# modFOC-Sensing.net
KiCad netlist of a schematic drawn in Altium Designer
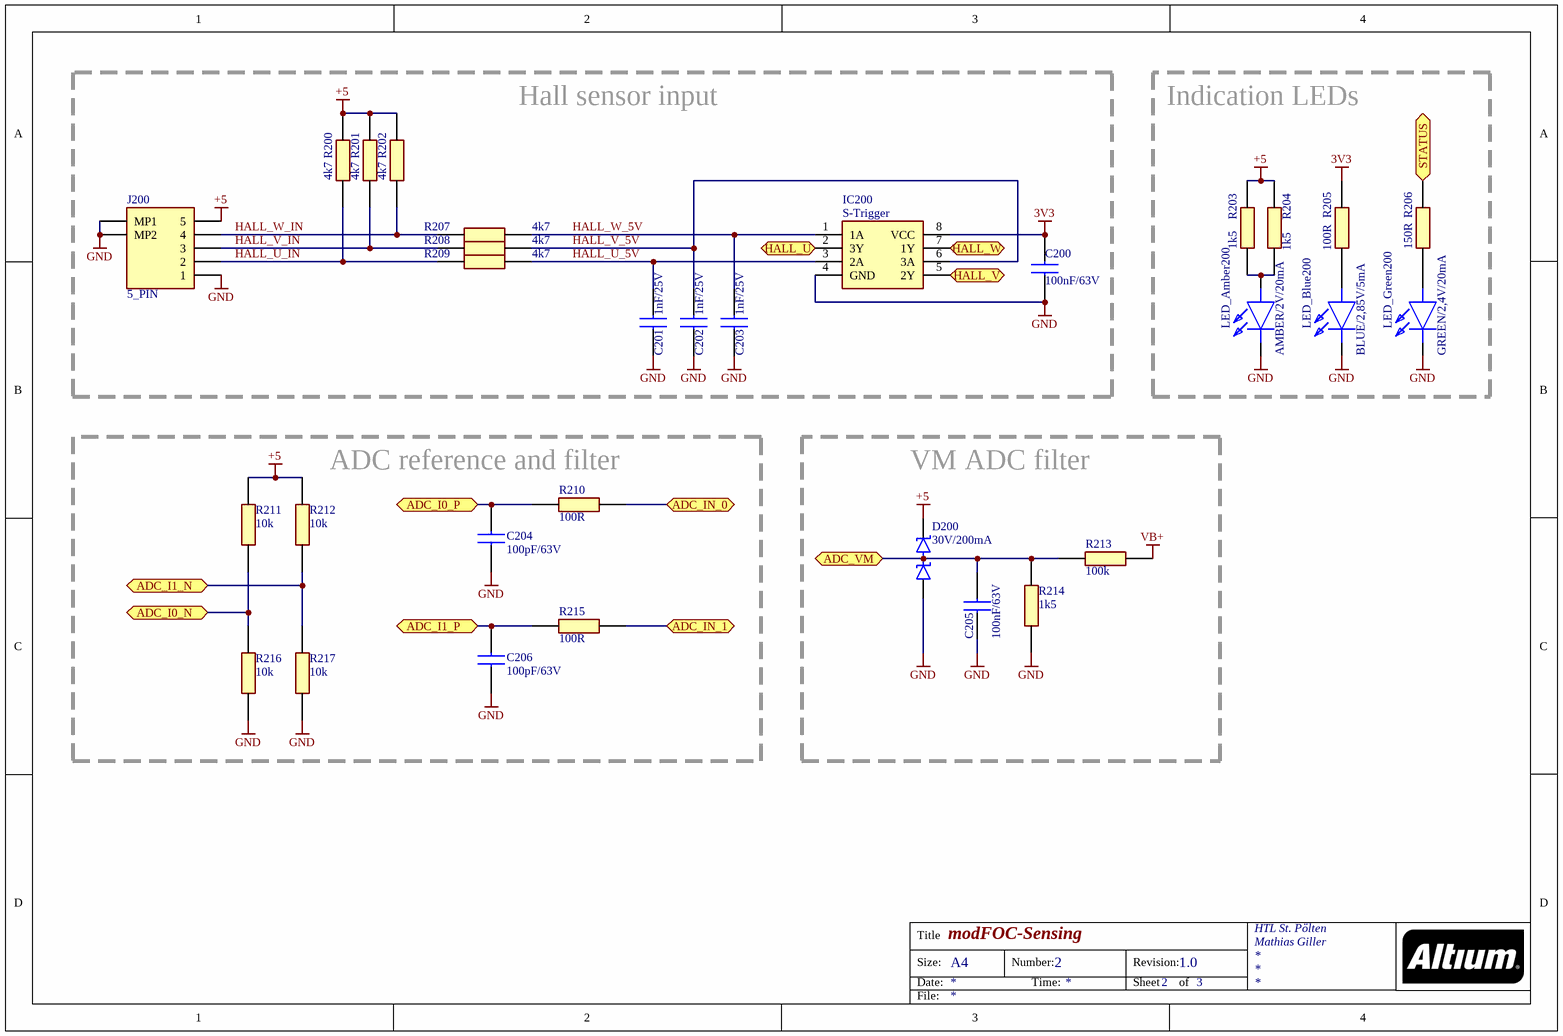
[diagram p0: modFOC-Sensing.SchDoc]

(export (version "E")
  (design (tool "Eeschema 10.0.6"))
  (components
    (comp (ref "C200")
      (value "100nF/63V")
      (footprint "CAPC1608X97N")
      (description "Capacitor")
      (fields
        (field (name "MANUFACTURER_PART_NUMBER") "VJ0603Y104JXJAC")
        (field (name "MOUSER PART NUMBER") "77-VJ0603Y104JXJAC")
      )
      (libsource (lib "Schlib1") (part "C0805C104MMREC7210"))
    )
    (comp (ref "C201")
      (value "1nF/25V")
      (footprint "CAPC1608X97N")
      (description "Capacitor")
      (fields
        (field (name "MANUFACTURER_PART_NUMBER") "GRM033R71E102KA01D")
        (field (name "MOUSER PART NUMBER") "81-GRM033R71E102KA1D")
      )
      (libsource (lib "Schlib1") (part "GRM033R71E102KA01D"))
    )
    (comp (ref "C202")
      (value "1nF/25V")
      (footprint "CAPC1608X97N")
      (description "Capacitor")
      (fields
        (field (name "MANUFACTURER_PART_NUMBER") "GRM033R71E102KA01D")
        (field (name "MOUSER PART NUMBER") "81-GRM033R71E102KA1D")
      )
      (libsource (lib "Schlib1") (part "GRM033R71E102KA01D"))
    )
    (comp (ref "C203")
      (value "1nF/25V")
      (footprint "CAPC1608X97N")
      (description "Capacitor")
      (fields
        (field (name "MANUFACTURER_PART_NUMBER") "GRM033R71E102KA01D")
        (field (name "MOUSER PART NUMBER") "81-GRM033R71E102KA1D")
      )
      (libsource (lib "Schlib1") (part "GRM033R71E102KA01D"))
    )
    (comp (ref "C204")
      (value "100pF/63V")
      (footprint "CAPC1608X87N")
      (description "Capacitor")
      (fields
        (field (name "MANUFACTURER_PART_NUMBER") "C0603C101K1HACTU")
        (field (name "MOUSER PART NUMBER") "80-C0603C101K1HACTU")
      )
      (libsource (lib "Schlib1") (part "C0603C101K1HACTU"))
    )
    (comp (ref "C205")
      (value "100nF/63V")
      (footprint "CAPC1608X97N")
      (description "Capacitor")
      (fields
        (field (name "MANUFACTURER_PART_NUMBER") "VJ0603Y104JXJAC")
        (field (name "MOUSER PART NUMBER") "77-VJ0603Y104JXJAC")
      )
      (libsource (lib "Schlib1") (part "C0805C104MMREC7210"))
    )
    (comp (ref "C206")
      (value "100pF/63V")
      (footprint "CAPC1608X87N")
      (description "Capacitor")
      (fields
        (field (name "MANUFACTURER_PART_NUMBER") "C0603C101K1HACTU")
        (field (name "MOUSER PART NUMBER") "80-C0603C101K1HACTU")
      )
      (libsource (lib "Schlib1") (part "C0603C101K1HACTU"))
    )
    (comp (ref "D200")
      (value "30V/200mA")
      (footprint "SOT95P240X110-3N")
      (description "Schottky Diode")
      (fields
        (field (name "MANUFACTURER_PART_NUMBER") "BAT54S")
        (field (name "MOUSER PART NUMBER") "583-BAT54S")
      )
      (libsource (lib "Schlib1") (part "BAT54S"))
    )
    (comp (ref "IC200")
      (value "S-Trigger")
      (footprint "SOP65P400X110-8N")
      (description "Integrated Circuit")
      (fields
        (field (name "MANUFACTURER_PART_NUMBER") "74LVC3G17DP,125")
        (field (name "MOUSER PART NUMBER") "771-LVC3G17DP125")
      )
      (libsource (lib "Schlib1") (part "74LVC3G17DP,125"))
    )
    (comp (ref "J200")
      (value "5_PIN")
      (footprint "DF13A5P125H21")
      (description "Connector")
      (fields
        (field (name "MANUFACTURER_PART_NUMBER") "DF13A-5P-1.25H(21)")
        (field (name "MOUSER PART NUMBER") "798-DF13A5P125H21")
      )
      (libsource (lib "Schlib1") (part "DF13A-5P-1.25H_21_"))
    )
    (comp (ref "LED_Amber200")
      (value "AMBER/2V/20mA")
      (footprint "LEDC1608X55N")
      (description "LED")
      (fields
        (field (name "MANUFACTURER_PART_NUMBER") "ASMT-RA45-AP932")
        (field (name "MOUSER PART NUMBER") "630-ASMT-RA45-AP932")
      )
      (libsource (lib "Schlib1") (part "ASMT-RA45-AP932"))
    )
    (comp (ref "LED_Blue200")
      (value "BLUE/2,85V/5mA")
      (footprint "LEDC1608X40N")
      (description "LED")
      (fields
        (field (name "MANUFACTURER_PART_NUMBER") "LB Q39G-L2OO-35-1")
        (field (name "MOUSER PART NUMBER") "720-LBQ39GL2N2351")
      )
      (libsource (lib "Schlib1") (part "LB_Q39G-L2OO-35-1"))
    )
    (comp (ref "LED_Green200")
      (value "GREEN/2,4V/20mA")
      (footprint "LGQ396PS35")
      (description "LED")
      (fields
        (field (name "MANUFACTURER_PART_NUMBER") "LG Q396-PS-35")
        (field (name "MOUSER PART NUMBER") "720-LGQ396A3964")
      )
      (libsource (lib "Schlib1") (part "LG_Q396-PS-35"))
    )
    (comp (ref "R200")
      (value "4k7")
      (footprint "RESC1608X55N")
      (description "Resistor")
      (fields
        (field (name "MANUFACTURER_PART_NUMBER") "CRCW06034K70JNEAC")
        (field (name "MOUSER PART NUMBER") "71-CRCW06034K70JNEAC")
      )
      (libsource (lib "") (part "CRCW06034K70JNEAC_1"))
    )
    (comp (ref "R201")
      (value "4k7")
      (footprint "RESC1608X55N")
      (description "Resistor")
      (fields
        (field (name "MANUFACTURER_PART_NUMBER") "CRCW06034K70JNEAC")
        (field (name "MOUSER PART NUMBER") "71-CRCW06034K70JNEAC")
      )
      (libsource (lib "") (part "CRCW06034K70JNEAC_1"))
    )
    (comp (ref "R202")
      (value "4k7")
      (footprint "RESC1608X55N")
      (description "Resistor")
      (fields
        (field (name "MANUFACTURER_PART_NUMBER") "CRCW06034K70JNEAC")
        (field (name "MOUSER PART NUMBER") "71-CRCW06034K70JNEAC")
      )
      (libsource (lib "") (part "CRCW06034K70JNEAC_1"))
    )
    (comp (ref "R203")
      (value "1k5")
      (footprint "RESC1608X55N")
      (description "Resistor")
      (fields (field (name "MANUFACTURER_PART_NUMBER") "ERJ1GNF1501C"))
      (libsource (lib "Schlib1") (part "ERJ1GNF1501C"))
    )
    (comp (ref "R204")
      (value "1k5")
      (footprint "RESC1608X55N")
      (description "Resistor")
      (fields (field (name "MANUFACTURER_PART_NUMBER") "ERJ1GNF1501C"))
      (libsource (lib "Schlib1") (part "ERJ1GNF1501C"))
    )
    (comp (ref "R205")
      (value "100R")
      (footprint "RESC1608X55N")
      (description "Resistor")
      (fields
        (field (name "MANUFACTURER_PART_NUMBER") "CRCW0603100RFKEAC")
        (field (name "MOUSER PART NUMBER") "71-CRCW0603100RFKEAC")
      )
      (libsource (lib "") (part "CRCW0603100RFKEAC_1"))
    )
    (comp (ref "R206")
      (value "150R")
      (footprint "RESC1608X55N")
      (description "Resistor")
      (fields
        (field (name "MANUFACTURER_PART_NUMBER") "SFR03EZPF1500")
        (field (name "MOUSER PART NUMBER") "755-SFR03EZPF1500")
      )
      (libsource (lib "Schlib1") (part "SFR03EZPF1500"))
    )
    (comp (ref "R207")
      (value "4k7")
      (footprint "RESC1608X55N")
      (description "Resistor")
      (fields
        (field (name "MANUFACTURER_PART_NUMBER") "CRCW06034K70JNEAC")
        (field (name "MOUSER PART NUMBER") "71-CRCW06034K70JNEAC")
      )
      (libsource (lib "Schlib1") (part "CRCW06034K70JNEAC"))
    )
    (comp (ref "R208")
      (value "4k7")
      (footprint "RESC1608X55N")
      (description "Resistor")
      (fields
        (field (name "MANUFACTURER_PART_NUMBER") "CRCW06034K70JNEAC")
        (field (name "MOUSER PART NUMBER") "71-CRCW06034K70JNEAC")
      )
      (libsource (lib "Schlib1") (part "CRCW06034K70JNEAC"))
    )
    (comp (ref "R209")
      (value "4k7")
      (footprint "RESC1608X55N")
      (description "Resistor")
      (fields
        (field (name "MANUFACTURER_PART_NUMBER") "CRCW06034K70JNEAC")
        (field (name "MOUSER PART NUMBER") "71-CRCW06034K70JNEAC")
      )
      (libsource (lib "Schlib1") (part "CRCW06034K70JNEAC"))
    )
    (comp (ref "R210")
      (value "100R")
      (footprint "RESC1608X55N")
      (description "Resistor")
      (fields
        (field (name "MANUFACTURER_PART_NUMBER") "CRCW0603100RFKEAC")
        (field (name "MOUSER PART NUMBER") "71-CRCW0603100RFKEAC")
      )
      (libsource (lib "Schlib1") (part "CRCW0603100RFKEAC"))
    )
    (comp (ref "R211")
      (value "10k")
      (footprint "RESC1608X55N")
      (description "Resistor")
      (fields
        (field (name "MANUFACTURER_PART_NUMBER") "RC0603FR-0710KL")
        (field (name "MOUSER PART NUMBER") "603-RC0603FR-0710KL")
      )
      (libsource (lib "") (part "RC0603FR-0710KL_1"))
    )
    (comp (ref "R212")
      (value "10k")
      (footprint "RESC1608X55N")
      (description "Resistor")
      (fields
        (field (name "MANUFACTURER_PART_NUMBER") "RC0603FR-0710KL")
        (field (name "MOUSER PART NUMBER") "603-RC0603FR-0710KL")
      )
      (libsource (lib "Schlib1") (part "RC0603FR-0710KL"))
    )
    (comp (ref "R213")
      (value "100k")
      (footprint "RESC1608X55N")
      (description "Resistor")
      (fields (field (name "MANUFACTURER_PART_NUMBER") "ERJ1GNF1003C"))
      (libsource (lib "Schlib1") (part "ERJ1GNF1003C"))
    )
    (comp (ref "R214")
      (value "1k5")
      (footprint "RESC1608X55N")
      (description "Resistor")
      (fields (field (name "MANUFACTURER_PART_NUMBER") "ERJ1GNF1501C"))
      (libsource (lib "Schlib1") (part "ERJ1GNF1501C"))
    )
    (comp (ref "R215")
      (value "100R")
      (footprint "RESC1608X55N")
      (description "Resistor")
      (fields
        (field (name "MANUFACTURER_PART_NUMBER") "CRCW0603100RFKEAC")
        (field (name "MOUSER PART NUMBER") "71-CRCW0603100RFKEAC")
      )
      (libsource (lib "Schlib1") (part "CRCW0603100RFKEAC"))
    )
    (comp (ref "R216")
      (value "10k")
      (footprint "RESC1608X55N")
      (description "Resistor")
      (fields
        (field (name "MANUFACTURER_PART_NUMBER") "RC0603FR-0710KL")
        (field (name "MOUSER PART NUMBER") "603-RC0603FR-0710KL")
      )
      (libsource (lib "Schlib1") (part "RC0603FR-0710KL"))
    )
    (comp (ref "R217")
      (value "10k")
      (footprint "RESC1608X55N")
      (description "Resistor")
      (fields
        (field (name "MANUFACTURER_PART_NUMBER") "RC0603FR-0710KL")
        (field (name "MOUSER PART NUMBER") "603-RC0603FR-0710KL")
      )
      (libsource (lib "Schlib1") (part "RC0603FR-0710KL"))
    )
  )
  (nets
    (net (code "1") (name "+5") (class "Default")
      (node (ref "D200") (pin "2") (pinfunction "K_2") (pintype "passive"))
      (node (ref "J200") (pin "5") (pinfunction "5_5") (pintype "passive"))
      (node (ref "R200") (pin "1") (pinfunction "1_1") (pintype "passive"))
      (node (ref "R201") (pin "1") (pinfunction "1_1") (pintype "passive"))
      (node (ref "R202") (pin "1") (pinfunction "1_1") (pintype "passive"))
      (node (ref "R203") (pin "2") (pinfunction "2_2") (pintype "passive"))
      (node (ref "R204") (pin "2") (pinfunction "2_2") (pintype "passive"))
      (node (ref "R211") (pin "2") (pinfunction "2_2") (pintype "passive"))
      (node (ref "R212") (pin "1") (pinfunction "1_1") (pintype "passive"))
    )
    (net (code "2") (name "/ADC_I0_N") (class "Default")
      (node (ref "R211") (pin "1") (pinfunction "1_1") (pintype "passive"))
      (node (ref "R216") (pin "1") (pinfunction "1_1") (pintype "passive"))
    )
    (net (code "3") (name "/ADC_I0_P") (class "Default")
      (node (ref "C204") (pin "2") (pinfunction "2_2") (pintype "passive"))
      (node (ref "R210") (pin "1") (pinfunction "1_1") (pintype "passive"))
    )
    (net (code "4") (name "/ADC_I1_N") (class "Default")
      (node (ref "R212") (pin "2") (pinfunction "2_2") (pintype "passive"))
      (node (ref "R217") (pin "1") (pinfunction "1_1") (pintype "passive"))
    )
    (net (code "5") (name "/ADC_I1_P") (class "Default")
      (node (ref "C206") (pin "2") (pinfunction "2_2") (pintype "passive"))
      (node (ref "R215") (pin "1") (pinfunction "1_1") (pintype "passive"))
    )
    (net (code "6") (name "/ADC_IN_0") (class "Default")
      (node (ref "R210") (pin "2") (pinfunction "2_2") (pintype "passive"))
    )
    (net (code "7") (name "/ADC_IN_1") (class "Default")
      (node (ref "R215") (pin "2") (pinfunction "2_2") (pintype "passive"))
    )
    (net (code "8") (name "/ADC_VM") (class "Default")
      (node (ref "C205") (pin "2") (pinfunction "2_2") (pintype "passive"))
      (node (ref "D200") (pin "3") (pinfunction "A/K_3") (pintype "passive"))
      (node (ref "R213") (pin "1") (pinfunction "1_1") (pintype "passive"))
      (node (ref "R214") (pin "2") (pinfunction "2_2") (pintype "passive"))
    )
    (net (code "9") (name "/HALL_U") (class "Default")
      (node (ref "IC200") (pin "2") (pinfunction "3Y_2") (pintype "passive"))
    )
    (net (code "10") (name "/HALL_U_5V") (class "Default")
      (node (ref "C201") (pin "1") (pinfunction "1_1") (pintype "passive"))
      (node (ref "IC200") (pin "3") (pinfunction "2A_3") (pintype "passive"))
      (node (ref "R209") (pin "2") (pinfunction "2_2") (pintype "passive"))
    )
    (net (code "11") (name "/HALL_U_IN") (class "Default")
      (node (ref "J200") (pin "2") (pinfunction "2_2") (pintype "passive"))
      (node (ref "R200") (pin "2") (pinfunction "2_2") (pintype "passive"))
      (node (ref "R209") (pin "1") (pinfunction "1_1") (pintype "passive"))
    )
    (net (code "12") (name "/HALL_V") (class "Default")
      (node (ref "IC200") (pin "5") (pinfunction "2Y_5") (pintype "passive"))
    )
    (net (code "13") (name "/HALL_V_5V") (class "Default")
      (node (ref "C202") (pin "1") (pinfunction "1_1") (pintype "passive"))
      (node (ref "IC200") (pin "6") (pinfunction "3A_6") (pintype "passive"))
      (node (ref "R208") (pin "2") (pinfunction "2_2") (pintype "passive"))
    )
    (net (code "14") (name "/HALL_V_IN") (class "Default")
      (node (ref "J200") (pin "3") (pinfunction "3_3") (pintype "passive"))
      (node (ref "R201") (pin "2") (pinfunction "2_2") (pintype "passive"))
      (node (ref "R208") (pin "1") (pinfunction "1_1") (pintype "passive"))
    )
    (net (code "15") (name "/HALL_W") (class "Default")
      (node (ref "IC200") (pin "7") (pinfunction "1Y_7") (pintype "passive"))
    )
    (net (code "16") (name "/HALL_W_5V") (class "Default")
      (node (ref "C203") (pin "1") (pinfunction "1_1") (pintype "passive"))
      (node (ref "IC200") (pin "1") (pinfunction "1A_1") (pintype "passive"))
      (node (ref "R207") (pin "2") (pinfunction "2_2") (pintype "passive"))
    )
    (net (code "17") (name "/HALL_W_IN") (class "Default")
      (node (ref "J200") (pin "4") (pinfunction "4_4") (pintype "passive"))
      (node (ref "R202") (pin "2") (pinfunction "2_2") (pintype "passive"))
      (node (ref "R207") (pin "1") (pinfunction "1_1") (pintype "passive"))
    )
    (net (code "18") (name "/STATUS") (class "Default")
      (node (ref "R206") (pin "2") (pinfunction "2_2") (pintype "passive"))
    )
    (net (code "19") (name "3V3") (class "Default")
      (node (ref "C200") (pin "2") (pinfunction "2_2") (pintype "passive"))
      (node (ref "IC200") (pin "8") (pinfunction "VCC_8") (pintype "passive"))
      (node (ref "R205") (pin "2") (pinfunction "2_2") (pintype "passive"))
    )
    (net (code "20") (name "GND") (class "Default")
      (node (ref "C200") (pin "1") (pinfunction "1_1") (pintype "passive"))
      (node (ref "C201") (pin "2") (pinfunction "2_2") (pintype "passive"))
      (node (ref "C202") (pin "2") (pinfunction "2_2") (pintype "passive"))
      (node (ref "C203") (pin "2") (pinfunction "2_2") (pintype "passive"))
      (node (ref "C204") (pin "1") (pinfunction "1_1") (pintype "passive"))
      (node (ref "C205") (pin "1") (pinfunction "1_1") (pintype "passive"))
      (node (ref "C206") (pin "1") (pinfunction "1_1") (pintype "passive"))
      (node (ref "D200") (pin "1") (pinfunction "A_1") (pintype "passive"))
      (node (ref "IC200") (pin "4") (pinfunction "GND_4") (pintype "passive"))
      (node (ref "J200") (pin "1") (pinfunction "1_1") (pintype "passive"))
      (node (ref "J200") (pin "MP1") (pinfunction "MP1_MP1") (pintype "passive"))
      (node (ref "J200") (pin "MP2") (pinfunction "MP2_MP2") (pintype "passive"))
      (node (ref "LED_Amber200") (pin "1") (pinfunction "K_1") (pintype "passive"))
      (node (ref "LED_Blue200") (pin "1") (pinfunction "K_1") (pintype "passive"))
      (node (ref "LED_Green200") (pin "1") (pinfunction "K_1") (pintype "passive"))
      (node (ref "R214") (pin "1") (pinfunction "1_1") (pintype "passive"))
      (node (ref "R216") (pin "2") (pinfunction "2_2") (pintype "passive"))
      (node (ref "R217") (pin "2") (pinfunction "2_2") (pintype "passive"))
    )
    (net (code "21") (name "Net-(LED_Amber200-A)") (class "Default")
      (node (ref "LED_Amber200") (pin "2") (pinfunction "A_2") (pintype "passive"))
      (node (ref "R203") (pin "1") (pinfunction "1_1") (pintype "passive"))
      (node (ref "R204") (pin "1") (pinfunction "1_1") (pintype "passive"))
    )
    (net (code "22") (name "Net-(LED_Blue200-A)") (class "Default")
      (node (ref "LED_Blue200") (pin "2") (pinfunction "A_2") (pintype "passive"))
      (node (ref "R205") (pin "1") (pinfunction "1_1") (pintype "passive"))
    )
    (net (code "23") (name "Net-(LED_Green200-A)") (class "Default")
      (node (ref "LED_Green200") (pin "2") (pinfunction "A_2") (pintype "passive"))
      (node (ref "R206") (pin "1") (pinfunction "1_1") (pintype "passive"))
    )
    (net (code "24") (name "VB+") (class "Default")
      (node (ref "R213") (pin "2") (pinfunction "2_2") (pintype "passive"))
    )
  )
)
